# BSPD.net
KiCad netlist of a schematic drawn in Altium Designer
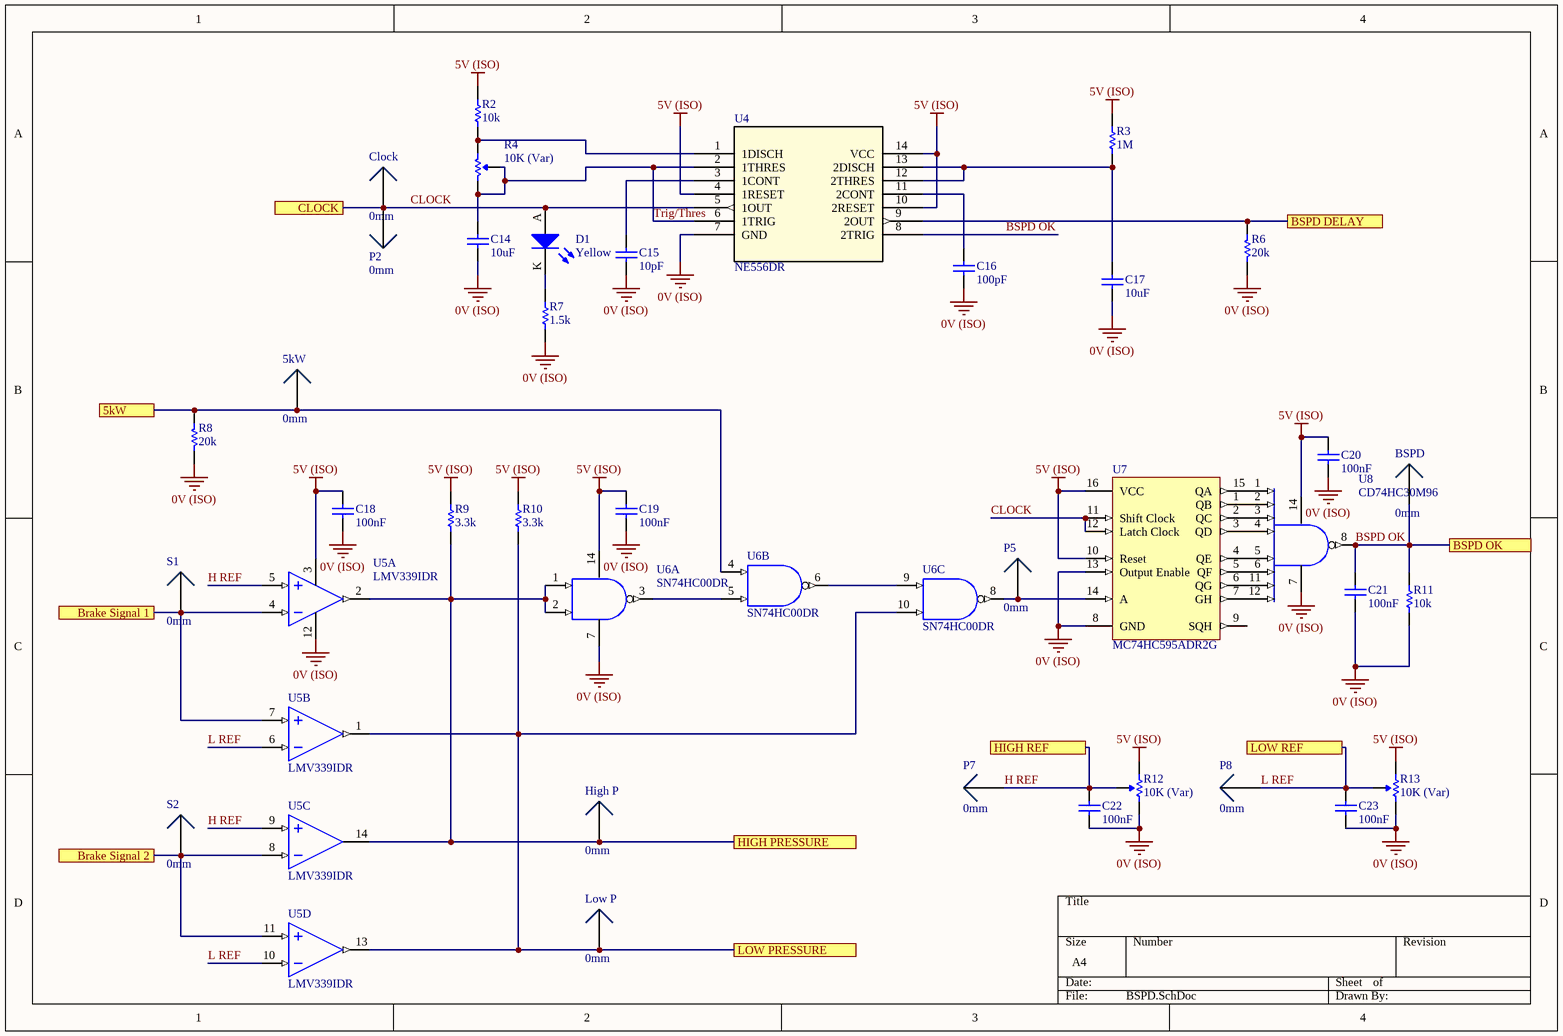
[diagram p0: BSPD.SchDoc]

(export (version "E")
  (design (tool "Eeschema 10.0.6"))
  (components
    (comp (ref "5kW")
      (value "0mm")
      (footprint "SMD Test Point")
      (fields (field (name "PART NUMBER") "SMD Test Point") (field (name "CONTACT") "NA"))
      (libsource (lib "ts_20-standard-connectors") (part "Test Point"))
    )
    (comp (ref "BSPD")
      (value "0mm")
      (footprint "SMD Test Point")
      (fields (field (name "PART NUMBER") "SMD Test Point") (field (name "CONTACT") "NA"))
      (libsource (lib "ts_20-standard-connectors") (part "Test Point"))
    )
    (comp (ref "C14")
      (value "10uF")
      (footprint "0805")
      (fields
        (field (name "PART NUMBER") "GRM21BR6YA106KE43L")
        (field (name "TOLERANCE") "10%")
        (field (name "MANUFACTURER") "muRata")
      )
      (libsource (lib "ts_20-standard-library") (part "Capacitor"))
    )
    (comp (ref "C15")
      (value "10pF")
      (footprint "0805")
      (fields
        (field (name "PART NUMBER") "GRM21A5C2E100JW01D")
        (field (name "TOLERANCE") "±5%")
        (field (name "MANUFACTURER") "muRata")
      )
      (libsource (lib "ts_20-standard-library") (part "Capacitor"))
    )
    (comp (ref "C16")
      (value "100pF")
      (footprint "0805")
      (fields
        (field (name "PART NUMBER") "GCM2165C1H101JA16D")
        (field (name "TOLERANCE") "±5%")
        (field (name "MANUFACTURER") "muRata")
      )
      (libsource (lib "ts_20-standard-library") (part "Capacitor"))
    )
    (comp (ref "C17")
      (value "10uF")
      (footprint "0805")
      (fields
        (field (name "PART NUMBER") "GRM21BR6YA106KE43L")
        (field (name "TOLERANCE") "10%")
        (field (name "MANUFACTURER") "muRata")
      )
      (libsource (lib "ts_20-standard-library") (part "Capacitor"))
    )
    (comp (ref "C18")
      (value "100nF")
      (footprint "0805")
      (fields
        (field (name "PART NUMBER") "GCM21BR71H104KA37L")
        (field (name "TOLERANCE") "±10%")
        (field (name "MANUFACTURER") "muRata")
      )
      (libsource (lib "ts_20-standard-library") (part "Capacitor"))
    )
    (comp (ref "C19")
      (value "100nF")
      (footprint "0805")
      (fields
        (field (name "PART NUMBER") "GCM21BR71E104KA37L")
        (field (name "TOLERANCE") "10%")
        (field (name "MANUFACTURER") "muRata")
      )
      (libsource (lib "ts_20-standard-library") (part "Capacitor"))
    )
    (comp (ref "C20")
      (value "100nF")
      (footprint "0805")
      (fields
        (field (name "PART NUMBER") "GCM21BR71H104KA37L")
        (field (name "TOLERANCE") "±10%")
        (field (name "MANUFACTURER") "muRata")
      )
      (libsource (lib "ts_20-standard-library") (part "Capacitor"))
    )
    (comp (ref "C21")
      (value "100nF")
      (footprint "0805")
      (fields
        (field (name "PART NUMBER") "GCM21BR71H104KA37L")
        (field (name "TOLERANCE") "±10%")
        (field (name "MANUFACTURER") "muRata")
      )
      (libsource (lib "ts_20-standard-library") (part "Capacitor"))
    )
    (comp (ref "C22")
      (value "100nF")
      (footprint "0805")
      (fields
        (field (name "PART NUMBER") "GCM21BR71H104KA37L")
        (field (name "TOLERANCE") "±10%")
        (field (name "MANUFACTURER") "muRata")
      )
      (libsource (lib "ts_20-standard-library") (part "Capacitor"))
    )
    (comp (ref "C23")
      (value "100nF")
      (footprint "0805")
      (fields
        (field (name "PART NUMBER") "GCM21BR71H104KA37L")
        (field (name "TOLERANCE") "±10%")
        (field (name "MANUFACTURER") "muRata")
      )
      (libsource (lib "ts_20-standard-library") (part "Capacitor"))
    )
    (comp (ref "Clock")
      (value "0mm")
      (footprint "SMD Test Point")
      (fields (field (name "PART NUMBER") "SMD Test Point") (field (name "CONTACT") "NA"))
      (libsource (lib "ts_20-standard-connectors") (part "Test Point"))
    )
    (comp (ref "D1")
      (value "Yellow")
      (footprint "0805 LED")
      (description "Yellow LED Indication - Discrete 1.75V 0805 (2012 Metric)")
      (fields (field (name "PART NUMBER") "SML-211YTT86") (field (name "MANUFACTURER") "ROHM Semiconductor"))
      (libsource (lib "ts_20-standard-library") (part "LED"))
    )
    (comp (ref "High P")
      (value "0mm")
      (footprint "SMD Test Point")
      (fields (field (name "PART NUMBER") "SMD Test Point") (field (name "CONTACT") "NA"))
      (libsource (lib "ts_20-standard-connectors") (part "Test Point"))
    )
    (comp (ref "Low P")
      (value "0mm")
      (footprint "SMD Test Point")
      (fields (field (name "PART NUMBER") "SMD Test Point") (field (name "CONTACT") "NA"))
      (libsource (lib "ts_20-standard-connectors") (part "Test Point"))
    )
    (comp (ref "P2")
      (value "0mm")
      (footprint "TH Test Point")
      (fields (field (name "PART NUMBER") "TH Test Point") (field (name "CONTACT") "NA"))
      (libsource (lib "ts_20-standard-connectors") (part "Test Point"))
    )
    (comp (ref "P5")
      (value "0mm")
      (footprint "SMD Test Point")
      (fields (field (name "PART NUMBER") "SMD Test Point") (field (name "CONTACT") "NA"))
      (libsource (lib "ts_20-standard-connectors") (part "Test Point"))
    )
    (comp (ref "P7")
      (value "0mm")
      (footprint "TH Test Point")
      (fields (field (name "PART NUMBER") "TH Test Point") (field (name "CONTACT") "NA"))
      (libsource (lib "ts_20-standard-connectors") (part "Test Point"))
    )
    (comp (ref "P8")
      (value "0mm")
      (footprint "TH Test Point")
      (fields (field (name "PART NUMBER") "TH Test Point") (field (name "CONTACT") "NA"))
      (libsource (lib "ts_20-standard-connectors") (part "Test Point"))
    )
    (comp (ref "R2")
      (value "10k")
      (footprint "0805")
      (fields
        (field (name "PART NUMBER") "RC0805FR0710KL")
        (field (name "MANUFACTURER") "YAGEO")
        (field (name "TOLERANCE") "0.01")
      )
      (libsource (lib "ts_20-standard-library") (part "Resistor"))
    )
    (comp (ref "R3")
      (value "1M")
      (footprint "0805")
      (fields
        (field (name "PART NUMBER") "RC0805FR071ML")
        (field (name "MANUFACTURER") "YAGEO")
        (field (name "TOLERANCE") "0.01")
      )
      (libsource (lib "ts_20-standard-library") (part "Resistor"))
    )
    (comp (ref "R4")
      (value "10K (Var)")
      (footprint "B 3296")
      (fields
        (field (name "PART NUMBER") "3296W-1-103LF")
        (field (name "MANUFACTURER") "Bournes Inc")
        (field (name "TOLERANCE") "0.1")
      )
      (libsource (lib "ts_20-standard-library") (part "Resistor (Potentiometer)"))
    )
    (comp (ref "R6")
      (value "20k")
      (footprint "0805")
      (fields
        (field (name "PART NUMBER") "RC0805FR0720KL")
        (field (name "MANUFACTURER") "YAGEO")
        (field (name "TOLERANCE") "0.01")
      )
      (libsource (lib "ts_20-standard-library") (part "Resistor"))
    )
    (comp (ref "R7")
      (value "1.5k")
      (footprint "0805")
      (fields
        (field (name "PART NUMBER") "RC0805FR071K5L")
        (field (name "MANUFACTURER") "YAGEO")
        (field (name "TOLERANCE") "0.01")
      )
      (libsource (lib "ts_20-standard-library") (part "Resistor"))
    )
    (comp (ref "R8")
      (value "20k")
      (footprint "0805")
      (fields
        (field (name "PART NUMBER") "RC0805FR0720KL")
        (field (name "MANUFACTURER") "YAGEO")
        (field (name "TOLERANCE") "0.01")
      )
      (libsource (lib "ts_20-standard-library") (part "Resistor"))
    )
    (comp (ref "R9")
      (value "3.3k")
      (footprint "0805")
      (fields
        (field (name "PART NUMBER") "RC0805FR073K3L")
        (field (name "MANUFACTURER") "YAGEO")
        (field (name "TOLERANCE") "0.01")
      )
      (libsource (lib "ts_20-standard-library") (part "Resistor"))
    )
    (comp (ref "R10")
      (value "3.3k")
      (footprint "0805")
      (fields
        (field (name "PART NUMBER") "RC0805FR073K3L")
        (field (name "MANUFACTURER") "YAGEO")
        (field (name "TOLERANCE") "0.01")
      )
      (libsource (lib "ts_20-standard-library") (part "Resistor"))
    )
    (comp (ref "R11")
      (value "10k")
      (footprint "0805")
      (fields
        (field (name "PART NUMBER") "RC0805FR0710KL")
        (field (name "MANUFACTURER") "YAGEO")
        (field (name "TOLERANCE") "0.01")
      )
      (libsource (lib "ts_20-standard-library") (part "Resistor"))
    )
    (comp (ref "R12")
      (value "10K (Var)")
      (footprint "B 3296")
      (fields
        (field (name "PART NUMBER") "3296W-1-103LF")
        (field (name "MANUFACTURER") "Bournes Inc")
        (field (name "TOLERANCE") "0.1")
      )
      (libsource (lib "ts_20-standard-library") (part "Resistor (Potentiometer)"))
    )
    (comp (ref "R13")
      (value "10K (Var)")
      (footprint "B 3296")
      (fields
        (field (name "PART NUMBER") "3296W-1-103LF")
        (field (name "MANUFACTURER") "Bournes Inc")
        (field (name "TOLERANCE") "0.1")
      )
      (libsource (lib "ts_20-standard-library") (part "Resistor (Potentiometer)"))
    )
    (comp (ref "S1")
      (value "0mm")
      (footprint "TH Test Point")
      (fields (field (name "PART NUMBER") "TH Test Point") (field (name "CONTACT") "NA"))
      (libsource (lib "ts_20-standard-connectors") (part "Test Point"))
    )
    (comp (ref "S2")
      (value "0mm")
      (footprint "TH Test Point")
      (fields (field (name "PART NUMBER") "TH Test Point") (field (name "CONTACT") "NA"))
      (libsource (lib "ts_20-standard-connectors") (part "Test Point"))
    )
    (comp (ref "U4")
      (value "NE556DR")
      (footprint "TI 14-SOIC")
      (description "IC OSC TIMER DUAL 100KHZ 14SOIC")
      (fields
        (field (name "MANUFACTURER") "Texas Instruments")
        (field (name "DIGIKEY PART NUMBER") "296-26240-1-ND")
      )
      (libsource (lib "ts_20-standard-library") (part "NE556DR"))
    )
    (comp (ref "U5")
      (value "LMV339IDR")
      (footprint "TI 14-SOIC")
      (description "Comparator General Purpose Open Collector 14-SOIC")
      (fields
        (field (name "MANUFACTURER") "Texas Instruments")
        (field (name "DIGIKEY PART NUMBER") "296-6611-2-ND")
      )
      (libsource (lib "ts_20-standard-library") (part "LMV339IDR"))
    )
    (comp (ref "U6")
      (value "SN74HC00DR")
      (footprint "TI 14-SOIC")
      (description "NAND Gate IC 4 Channel 14-SOIC")
      (fields
        (field (name "MANUFACTURER") "Texas Instruments")
        (field (name "DIGIKEY PART NUMBER") "296-1187-2-ND")
      )
      (libsource (lib "ts_20-standard-library") (part "SN74HC00DR"))
    )
    (comp (ref "U7")
      (value "MC74HC595ADR2G")
      (footprint "ON 16-SOIC")
      (description "IC SHIFT REGISTR 8BIT 3ST 16SOIC")
      (fields
        (field (name "MANUFACTURER") "ON Semiconductor")
        (field (name "DIGIKEY PART NUMBER") "MC74HC595ADR2GOSCT-ND")
      )
      (libsource (lib "ts_20-standard-library") (part "MC74HC595ADR2G"))
    )
    (comp (ref "U8")
      (value "CD74HC30M96")
      (footprint "TI 14-SOIC")
      (description "IC GATE NAND 1CH 8-INP 14SOIC")
      (fields
        (field (name "MANUFACTURER") "Texas Instruments")
        (field (name "DIGIKEY PART NUMBER") "296-14521-1-ND")
      )
      (libsource (lib "ts_20-standard-library") (part "CD74HC30M96"))
    )
  )
  (nets
    (net (code "1") (name "/5kW") (class "Default")
      (node (ref "5kW") (pin "1") (pinfunction "1_1") (pintype "passive"))
      (node (ref "R8") (pin "1") (pinfunction "1_1") (pintype "passive"))
      (node (ref "U6") (pin "4") (pinfunction "2A_4") (pintype "input"))
    )
    (net (code "2") (name "/BSPD DELAY") (class "Default")
      (node (ref "R6") (pin "1") (pinfunction "1_1") (pintype "passive"))
      (node (ref "U4") (pin "9") (pinfunction "2OUT_9") (pintype "output"))
    )
    (net (code "3") (name "/BSPD OK") (class "Default")
      (node (ref "BSPD") (pin "1") (pinfunction "1_1") (pintype "passive"))
      (node (ref "C21") (pin "2") (pinfunction "2_2") (pintype "passive"))
      (node (ref "R11") (pin "2") (pinfunction "2_2") (pintype "passive"))
      (node (ref "U4") (pin "8") (pinfunction "2TRIG_8") (pintype "passive"))
      (node (ref "U8") (pin "8") (pinfunction "Output_8") (pintype "output"))
    )
    (net (code "4") (name "/Brake Signal 1") (class "Default")
      (node (ref "S1") (pin "1") (pinfunction "1_1") (pintype "passive"))
      (node (ref "U5") (pin "4") (pinfunction "IN_A-_4") (pintype "input"))
      (node (ref "U5") (pin "7") (pinfunction "IN_B+_7") (pintype "input"))
    )
    (net (code "5") (name "/Brake Signal 2") (class "Default")
      (node (ref "S2") (pin "1") (pinfunction "1_1") (pintype "passive"))
      (node (ref "U5") (pin "11") (pinfunction "IN_D+_11") (pintype "input"))
      (node (ref "U5") (pin "8") (pinfunction "IN_C-_8") (pintype "input"))
    )
    (net (code "6") (name "/CLOCK") (class "Default")
      (node (ref "Clock") (pin "1") (pinfunction "1_1") (pintype "passive"))
      (node (ref "D1") (pin "A") (pinfunction "A_A") (pintype "passive"))
      (node (ref "P2") (pin "1") (pinfunction "1_1") (pintype "passive"))
      (node (ref "U4") (pin "5") (pinfunction "1OUT_5") (pintype "output"))
      (node (ref "U7") (pin "11") (pinfunction "Shift_Clock_11") (pintype "input"))
      (node (ref "U7") (pin "12") (pinfunction "Latch_Clock_12") (pintype "input"))
    )
    (net (code "7") (name "/H REF") (class "Default")
      (node (ref "C22") (pin "2") (pinfunction "2_2") (pintype "passive"))
      (node (ref "P7") (pin "1") (pinfunction "1_1") (pintype "passive"))
      (node (ref "R12") (pin "2") (pinfunction "Wiper_2") (pintype "passive"))
      (node (ref "U5") (pin "5") (pinfunction "IN_A+_5") (pintype "input"))
      (node (ref "U5") (pin "9") (pinfunction "IN_C+_9") (pintype "input"))
    )
    (net (code "8") (name "/HIGH PRESSURE") (class "Default")
      (node (ref "High P") (pin "1") (pinfunction "1_1") (pintype "passive"))
      (node (ref "R9") (pin "1") (pinfunction "1_1") (pintype "passive"))
      (node (ref "U5") (pin "14") (pinfunction "OUT_C_14") (pintype "passive"))
      (node (ref "U5") (pin "2") (pinfunction "OUT_A_2") (pintype "output"))
      (node (ref "U6") (pin "1") (pinfunction "1A_1") (pintype "input"))
      (node (ref "U6") (pin "2") (pinfunction "1B_2") (pintype "input"))
    )
    (net (code "9") (name "/L REF") (class "Default")
      (node (ref "C23") (pin "2") (pinfunction "2_2") (pintype "passive"))
      (node (ref "P8") (pin "1") (pinfunction "1_1") (pintype "passive"))
      (node (ref "R13") (pin "2") (pinfunction "Wiper_2") (pintype "passive"))
      (node (ref "U5") (pin "10") (pinfunction "IN_D-_10") (pintype "input"))
      (node (ref "U5") (pin "6") (pinfunction "IN_B-_6") (pintype "input"))
    )
    (net (code "10") (name "/LOW PRESSURE") (class "Default")
      (node (ref "Low P") (pin "1") (pinfunction "1_1") (pintype "passive"))
      (node (ref "R10") (pin "1") (pinfunction "1_1") (pintype "passive"))
      (node (ref "U5") (pin "1") (pinfunction "OUT_B_1") (pintype "output"))
      (node (ref "U5") (pin "13") (pinfunction "OUT_D_13") (pintype "output"))
      (node (ref "U6") (pin "10") (pinfunction "3B_10") (pintype "input"))
    )
    (net (code "11") (name "/Trig{slash}Thres") (class "Default")
      (node (ref "C14") (pin "2") (pinfunction "2_2") (pintype "passive"))
      (node (ref "R4") (pin "1") (pinfunction "CCW_1") (pintype "passive"))
      (node (ref "R4") (pin "2") (pinfunction "Wiper_2") (pintype "passive"))
      (node (ref "U4") (pin "2") (pinfunction "1THRES_2") (pintype "passive"))
      (node (ref "U4") (pin "6") (pinfunction "1TRIG_6") (pintype "passive"))
    )
    (net (code "12") (name "0V (ISO)") (class "Default")
      (node (ref "C14") (pin "1") (pinfunction "1_1") (pintype "passive"))
      (node (ref "C15") (pin "1") (pinfunction "1_1") (pintype "passive"))
      (node (ref "C16") (pin "1") (pinfunction "1_1") (pintype "passive"))
      (node (ref "C17") (pin "1") (pinfunction "1_1") (pintype "passive"))
      (node (ref "C18") (pin "1") (pinfunction "1_1") (pintype "passive"))
      (node (ref "C19") (pin "1") (pinfunction "1_1") (pintype "passive"))
      (node (ref "C20") (pin "1") (pinfunction "1_1") (pintype "passive"))
      (node (ref "C21") (pin "1") (pinfunction "1_1") (pintype "passive"))
      (node (ref "C22") (pin "1") (pinfunction "1_1") (pintype "passive"))
      (node (ref "C23") (pin "1") (pinfunction "1_1") (pintype "passive"))
      (node (ref "R11") (pin "1") (pinfunction "1_1") (pintype "passive"))
      (node (ref "R12") (pin "1") (pinfunction "CCW_1") (pintype "passive"))
      (node (ref "R13") (pin "1") (pinfunction "CCW_1") (pintype "passive"))
      (node (ref "R6") (pin "2") (pinfunction "2_2") (pintype "passive"))
      (node (ref "R7") (pin "1") (pinfunction "1_1") (pintype "passive"))
      (node (ref "R8") (pin "2") (pinfunction "2_2") (pintype "passive"))
      (node (ref "U4") (pin "7") (pinfunction "GND_7") (pintype "power_in"))
      (node (ref "U5") (pin "12") (pinfunction "V-_12") (pintype "power_in"))
      (node (ref "U6") (pin "7") (pinfunction "GND_7") (pintype "power_in"))
      (node (ref "U7") (pin "13") (pinfunction "Output_Enable_13") (pintype "input"))
      (node (ref "U7") (pin "8") (pinfunction "GND_8") (pintype "power_in"))
      (node (ref "U8") (pin "7") (pinfunction "GND_7") (pintype "power_in"))
    )
    (net (code "13") (name "5V (ISO)") (class "Default")
      (node (ref "C18") (pin "2") (pinfunction "2_2") (pintype "passive"))
      (node (ref "C19") (pin "2") (pinfunction "2_2") (pintype "passive"))
      (node (ref "C20") (pin "2") (pinfunction "2_2") (pintype "passive"))
      (node (ref "R10") (pin "2") (pinfunction "2_2") (pintype "passive"))
      (node (ref "R12") (pin "3") (pinfunction "CW_3") (pintype "passive"))
      (node (ref "R13") (pin "3") (pinfunction "CW_3") (pintype "passive"))
      (node (ref "R2") (pin "2") (pinfunction "2_2") (pintype "passive"))
      (node (ref "R3") (pin "2") (pinfunction "2_2") (pintype "passive"))
      (node (ref "R9") (pin "2") (pinfunction "2_2") (pintype "passive"))
      (node (ref "U4") (pin "10") (pinfunction "2RESET_10") (pintype "passive"))
      (node (ref "U4") (pin "14") (pinfunction "VCC_14") (pintype "power_in"))
      (node (ref "U4") (pin "4") (pinfunction "1RESET_4") (pintype "passive"))
      (node (ref "U5") (pin "3") (pinfunction "V+_3") (pintype "power_in"))
      (node (ref "U6") (pin "14") (pinfunction "VCC_14") (pintype "power_in"))
      (node (ref "U7") (pin "10") (pinfunction "Reset_10") (pintype "input"))
      (node (ref "U7") (pin "16") (pinfunction "VCC_16") (pintype "power_in"))
      (node (ref "U8") (pin "14") (pinfunction "VCC_14") (pintype "power_in"))
    )
    (net (code "14") (name "Net-(D1-PadK)") (class "Default")
      (node (ref "D1") (pin "K") (pinfunction "K_K") (pintype "passive"))
      (node (ref "R7") (pin "2") (pinfunction "2_2") (pintype "passive"))
    )
    (net (code "15") (name "Net-(R4-CW)") (class "Default")
      (node (ref "R2") (pin "1") (pinfunction "1_1") (pintype "passive"))
      (node (ref "R4") (pin "3") (pinfunction "CW_3") (pintype "passive"))
      (node (ref "U4") (pin "1") (pinfunction "1DISCH_1") (pintype "passive"))
    )
    (net (code "16") (name "Net-(U4-1CONT)") (class "Default")
      (node (ref "C15") (pin "2") (pinfunction "2_2") (pintype "passive"))
      (node (ref "U4") (pin "3") (pinfunction "1CONT_3") (pintype "passive"))
    )
    (net (code "17") (name "Net-(U4-2CONT)") (class "Default")
      (node (ref "C16") (pin "2") (pinfunction "2_2") (pintype "passive"))
      (node (ref "U4") (pin "11") (pinfunction "2CONT_11") (pintype "passive"))
    )
    (net (code "18") (name "Net-(U4-2DISCH)") (class "Default")
      (node (ref "C17") (pin "2") (pinfunction "2_2") (pintype "passive"))
      (node (ref "R3") (pin "1") (pinfunction "1_1") (pintype "passive"))
      (node (ref "U4") (pin "12") (pinfunction "2THRES_12") (pintype "passive"))
      (node (ref "U4") (pin "13") (pinfunction "2DISCH_13") (pintype "passive"))
    )
    (net (code "19") (name "Net-(U6A-1Y)") (class "Default")
      (node (ref "U6") (pin "3") (pinfunction "1Y_3") (pintype "output"))
      (node (ref "U6") (pin "5") (pinfunction "2B_5") (pintype "input"))
    )
    (net (code "20") (name "Net-(U6B-2Y)") (class "Default")
      (node (ref "U6") (pin "6") (pinfunction "2Y_6") (pintype "output"))
      (node (ref "U6") (pin "9") (pinfunction "3A_9") (pintype "input"))
    )
    (net (code "21") (name "Net-(U6C-3Y)") (class "Default")
      (node (ref "P5") (pin "1") (pinfunction "1_1") (pintype "passive"))
      (node (ref "U6") (pin "8") (pinfunction "3Y_8") (pintype "output"))
      (node (ref "U7") (pin "14") (pinfunction "A_14") (pintype "input"))
    )
    (net (code "22") (name "Net-(U7-GH)") (class "Default")
      (node (ref "U7") (pin "7") (pinfunction "GH_7") (pintype "output"))
      (node (ref "U8") (pin "12") (pinfunction "Input_12") (pintype "input"))
    )
    (net (code "23") (name "Net-(U7-QA)") (class "Default")
      (node (ref "U7") (pin "15") (pinfunction "QA_15") (pintype "output"))
      (node (ref "U8") (pin "1") (pinfunction "Input_1") (pintype "input"))
    )
    (net (code "24") (name "Net-(U7-QB)") (class "Default")
      (node (ref "U7") (pin "1") (pinfunction "QB_1") (pintype "output"))
      (node (ref "U8") (pin "2") (pinfunction "Input_2") (pintype "input"))
    )
    (net (code "25") (name "Net-(U7-QC)") (class "Default")
      (node (ref "U7") (pin "2") (pinfunction "QC_2") (pintype "output"))
      (node (ref "U8") (pin "3") (pinfunction "Input_3") (pintype "input"))
    )
    (net (code "26") (name "Net-(U7-QD)") (class "Default")
      (node (ref "U7") (pin "3") (pinfunction "QD_3") (pintype "output"))
      (node (ref "U8") (pin "4") (pinfunction "Input_4") (pintype "input"))
    )
    (net (code "27") (name "Net-(U7-QE)") (class "Default")
      (node (ref "U7") (pin "4") (pinfunction "QE_4") (pintype "output"))
      (node (ref "U8") (pin "5") (pinfunction "Input_5") (pintype "input"))
    )
    (net (code "28") (name "Net-(U7-QF)") (class "Default")
      (node (ref "U7") (pin "5") (pinfunction "QF_5") (pintype "output"))
      (node (ref "U8") (pin "6") (pinfunction "Input_6") (pintype "input"))
    )
    (net (code "29") (name "Net-(U7-QG)") (class "Default")
      (node (ref "U7") (pin "6") (pinfunction "QG_6") (pintype "output"))
      (node (ref "U8") (pin "11") (pinfunction "Input_11") (pintype "input"))
    )
    (net (code "30") (name "unconnected-(U7-SQH-Pad9)") (class "Default")
      (node (ref "U7") (pin "9") (pinfunction "SQH_9") (pintype "output"))
    )
  )
)
